# USB3300.net
KiCad netlist of a schematic drawn in Altium Designer
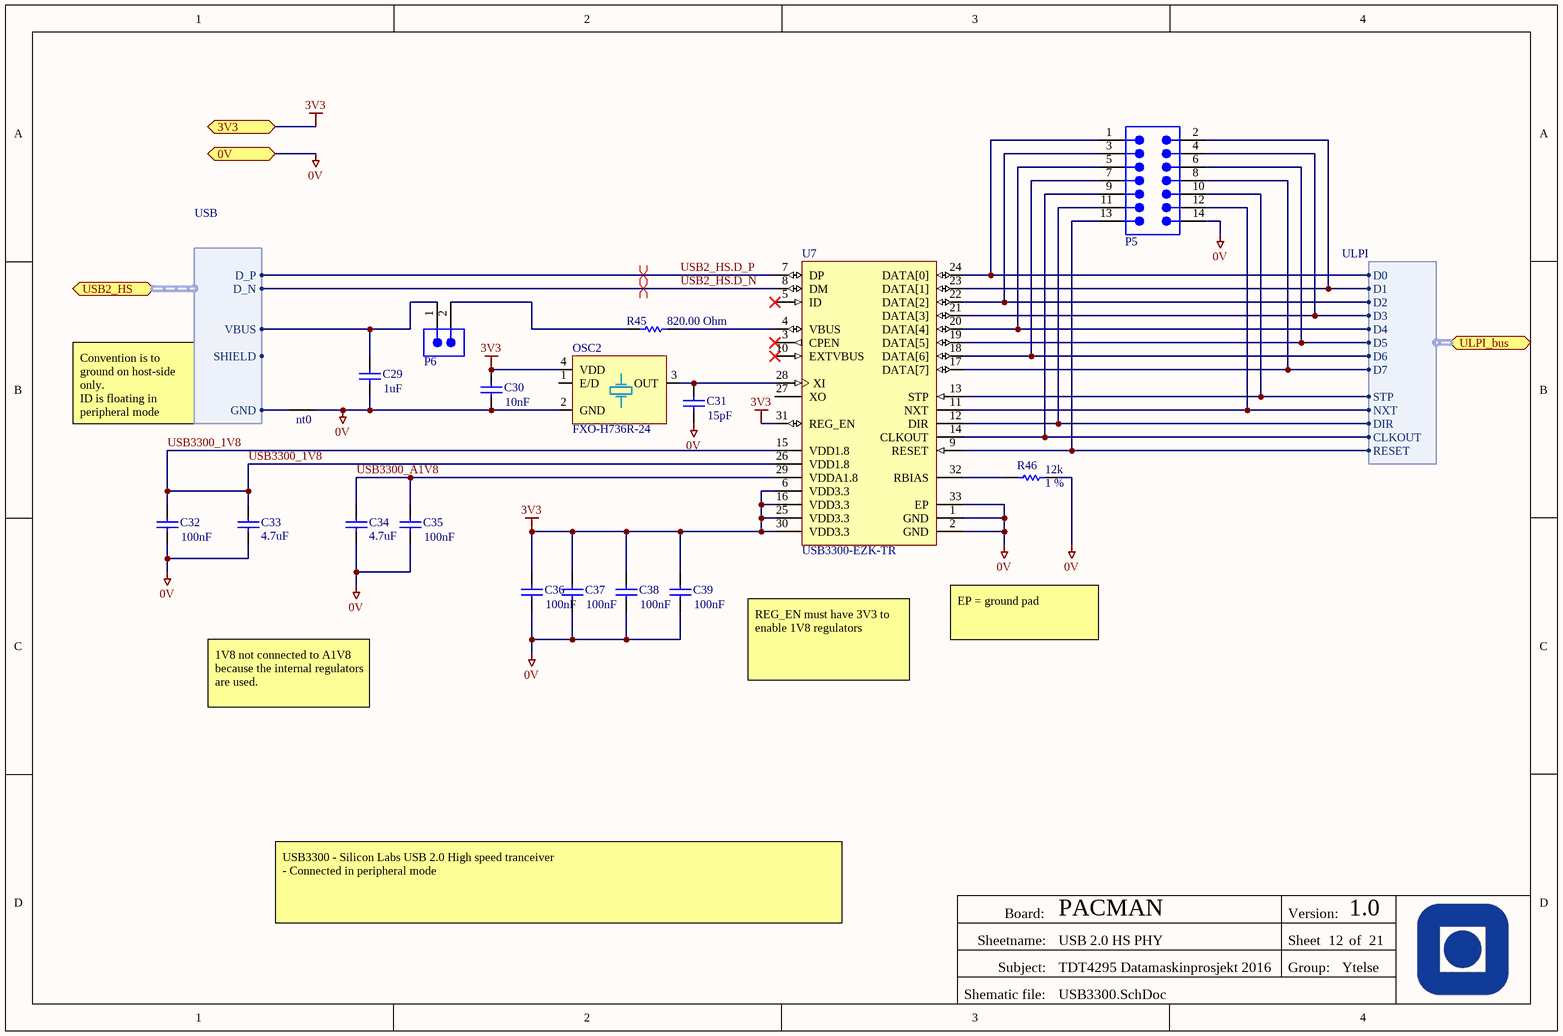
[diagram p0: USB3300.SchDoc]

(export (version "E")
  (design (tool "Eeschema 10.0.6"))
  (components
    (comp (ref "C29")
      (value "1uF")
      (footprint "CAPC0603(1608)100_M")
      (description "CAP 1uF 16V ±5% 0603 (1608 Metric) Thickness 1mm SMD")
      (fields (field (name "TOLERANCE") "Â±5%") (field (name "Comment") "CAP 1uF 16V 0603(1608)"))
      (libsource (lib "Altium Content Vault") (part "CMP-1035-02736-1"))
    )
    (comp (ref "C30")
      (value "10nF")
      (footprint "CAPC0603(1608)100_L")
      (description "CAP 10nF 16V ±1% 0603 (1608 Metric) Thickness 1mm SMD")
      (fields (field (name "TOLERANCE") "Â±1%") (field (name "Comment") "CAP 10nF 16V 0603(1608)"))
      (libsource (lib "Altium Content Vault") (part "CMP-1035-02309-1"))
    )
    (comp (ref "C31")
      (value "15pF")
      (footprint "CAPC0603(1608)100_M")
      (description "CAP 15pF 16V ±0.25pF 0603 (1608 Metric) Thickness 1mm SMD")
      (fields (field (name "TOLERANCE") "Â±0.25pF") (field (name "Comment") "CAP 15pF 16V 0603(1608)"))
      (libsource (lib "Altium Content Vault") (part "CMP-1035-00665-1"))
    )
    (comp (ref "C32")
      (value "100nF")
      (footprint "CAPC0603(1608)100_M")
      (description "CAP 100nF 16V ±5% 0603 (1608 Metric) Thickness 1mm SMD")
      (fields (field (name "TOLERANCE") "Â±5%") (field (name "Comment") "CAP 100nF 16V 0603(1608)"))
      (libsource (lib "Altium Content Vault") (part "CMP-1035-02583-1"))
    )
    (comp (ref "C33")
      (value "4.7uF")
      (footprint "CAPC0603(1608)100_M")
      (description "CAP 4.7uF 16V ±10% 0603 (1608 Metric) Thickness 1mm SMD")
      (fields (field (name "TOLERANCE") "Â±10%") (field (name "Comment") "CAP 4.7uF 16V 0603(1608)"))
      (libsource (lib "Altium Content Vault") (part "CMP-1035-02788-1"))
    )
    (comp (ref "C34")
      (value "4.7uF")
      (footprint "CAPC0603(1608)100_M")
      (description "CAP 4.7uF 16V ±10% 0603 (1608 Metric) Thickness 1mm SMD")
      (fields (field (name "TOLERANCE") "Â±10%") (field (name "Comment") "CAP 4.7uF 16V 0603(1608)"))
      (libsource (lib "Altium Content Vault") (part "CMP-1035-02788-1"))
    )
    (comp (ref "C35")
      (value "100nF")
      (footprint "CAPC0603(1608)100_M")
      (description "CAP 100nF 16V ±5% 0603 (1608 Metric) Thickness 1mm SMD")
      (fields (field (name "TOLERANCE") "Â±5%") (field (name "Comment") "CAP 100nF 16V 0603(1608)"))
      (libsource (lib "Altium Content Vault") (part "CMP-1035-02583-1"))
    )
    (comp (ref "C36")
      (value "100nF")
      (footprint "CAPC0603(1608)100_M")
      (description "CAP 100nF 16V ±5% 0603 (1608 Metric) Thickness 1mm SMD")
      (fields (field (name "TOLERANCE") "Â±5%") (field (name "Comment") "CAP 100nF 16V 0603(1608)"))
      (libsource (lib "Altium Content Vault") (part "CMP-1035-02583-1"))
    )
    (comp (ref "C37")
      (value "100nF")
      (footprint "CAPC0603(1608)100_M")
      (description "CAP 100nF 16V ±5% 0603 (1608 Metric) Thickness 1mm SMD")
      (fields (field (name "TOLERANCE") "Â±5%") (field (name "Comment") "CAP 100nF 16V 0603(1608)"))
      (libsource (lib "Altium Content Vault") (part "CMP-1035-02583-1"))
    )
    (comp (ref "C38")
      (value "100nF")
      (footprint "CAPC0603(1608)100_M")
      (description "CAP 100nF 16V ±5% 0603 (1608 Metric) Thickness 1mm SMD")
      (fields (field (name "TOLERANCE") "Â±5%") (field (name "Comment") "CAP 100nF 16V 0603(1608)"))
      (libsource (lib "Altium Content Vault") (part "CMP-1035-02583-1"))
    )
    (comp (ref "C39")
      (value "100nF")
      (footprint "CAPC0603(1608)100_M")
      (description "CAP 100nF 16V ±5% 0603 (1608 Metric) Thickness 1mm SMD")
      (fields (field (name "TOLERANCE") "Â±5%") (field (name "Comment") "CAP 100nF 16V 0603(1608)"))
      (libsource (lib "Altium Content Vault") (part "CMP-1035-02583-1"))
    )
    (comp (ref "nt0")
      (value "net tie")
      (footprint "net tie")
      (description "used to connect nets without transferring net name")
      (libsource (lib "dmpro16lib") (part "net tie"))
    )
    (comp (ref "OSC2")
      (value "FXO-H736R-24")
      (footprint "FXO-HC73")
      (libsource (lib "dmpro16lib") (part "FXO-H736R-24"))
    )
    (comp (ref "P5")
      (value "HTSW-107-42-F-D")
      (footprint "SMTC-HTSW-107-42-X-D")
      (fields (field (name "MANUFACTURER") "Samtec"))
      (libsource (lib "Altium Content Vault") (part "CMP-1024-00062-1"))
    )
    (comp (ref "P6")
      (value "TSW-102-26-L-S")
      (footprint "SMTC-TSW-102-26-XX-S")
      (description "0.025\" SQ Post Header, Through-hole, Vertical, -55 to 125 degC, 2.54 mm Pitch, 2-Pin, Male, RoHS")
      (fields (field (name "MANUFACTURER") "Samtec"))
      (libsource (lib "Altium Content Vault") (part "CMP-1024-00330-1"))
    )
    (comp (ref "R45")
      (value "820.00 Ohm")
      (footprint "RESC0603(1608)_N")
      (description "820R 0.1W 5% 0603 (1608 Metric)  SMD")
      (fields (field (name "TOLERANCE") "5 %") (field (name "POWER") "0.1 W"))
      (libsource (lib "Altium Content Vault") (part "CMP-1012-00072-1"))
    )
    (comp (ref "R46")
      (value "12k")
      (footprint "RESC0603(1608)_L")
      (description "12K 0.1W 1% 0603 (1608 Metric)  SMD")
      (fields
        (field (name "TOLERANCE") "1 %")
        (field (name "POWER") "0.1 W")
        (field (name "Comment") "12K 1% 0603(1608)")
      )
      (libsource (lib "Altium Content Vault") (part "CMP-1012-00631-1"))
    )
    (comp (ref "U7")
      (value "USB3300-EZK-TR")
      (footprint "MCHP-QFN-32-5x5_V2")
      (fields (field (name "GENERIC PART NUMBER") "USB3300"))
      (libsource (lib "Altium Content Vault") (part "MCHP-USB3300-QFN-32"))
    )
  )
  (nets
    (net (code "3") (name "/CLKOUT") (class "Default")
      (node (ref "P5") (pin "9") (pinfunction "9_9") (pintype "passive"))
      (node (ref "U7") (pin "14") (pinfunction "CLKOUT_14") (pintype "tri_state"))
    )
    (net (code "4") (name "/D0") (class "Default")
      (node (ref "P5") (pin "1") (pinfunction "1_1") (pintype "passive"))
      (node (ref "U7") (pin "24") (pinfunction "DATA[0]_24") (pintype "bidirectional"))
    )
    (net (code "5") (name "/D1") (class "Default")
      (node (ref "P5") (pin "2") (pinfunction "2_2") (pintype "passive"))
      (node (ref "U7") (pin "23") (pinfunction "DATA[1]_23") (pintype "bidirectional"))
    )
    (net (code "6") (name "/D2") (class "Default")
      (node (ref "P5") (pin "3") (pinfunction "3_3") (pintype "passive"))
      (node (ref "U7") (pin "22") (pinfunction "DATA[2]_22") (pintype "bidirectional"))
    )
    (net (code "7") (name "/D3") (class "Default")
      (node (ref "P5") (pin "4") (pinfunction "4_4") (pintype "passive"))
      (node (ref "U7") (pin "21") (pinfunction "DATA[3]_21") (pintype "bidirectional"))
    )
    (net (code "8") (name "/D4") (class "Default")
      (node (ref "P5") (pin "5") (pinfunction "5_5") (pintype "passive"))
      (node (ref "U7") (pin "20") (pinfunction "DATA[4]_20") (pintype "bidirectional"))
    )
    (net (code "9") (name "/D5") (class "Default")
      (node (ref "P5") (pin "6") (pinfunction "6_6") (pintype "passive"))
      (node (ref "U7") (pin "19") (pinfunction "DATA[5]_19") (pintype "bidirectional"))
    )
    (net (code "10") (name "/D6") (class "Default")
      (node (ref "P5") (pin "7") (pinfunction "7_7") (pintype "passive"))
      (node (ref "U7") (pin "18") (pinfunction "DATA[6]_18") (pintype "bidirectional"))
    )
    (net (code "11") (name "/D7") (class "Default")
      (node (ref "P5") (pin "8") (pinfunction "8_8") (pintype "passive"))
      (node (ref "U7") (pin "17") (pinfunction "DATA[7]_17") (pintype "bidirectional"))
    )
    (net (code "12") (name "/DIR") (class "Default")
      (node (ref "P5") (pin "11") (pinfunction "11_11") (pintype "passive"))
      (node (ref "U7") (pin "12") (pinfunction "DIR_12") (pintype "tri_state"))
    )
    (net (code "13") (name "/GND") (class "Default")
      (node (ref "nt0") (pin "0") (pinfunction "0_0") (pintype "passive"))
    )
    (net (code "14") (name "/NXT") (class "Default")
      (node (ref "P5") (pin "12") (pinfunction "12_12") (pintype "passive"))
      (node (ref "U7") (pin "11") (pinfunction "NXT_11") (pintype "tri_state"))
    )
    (net (code "15") (name "/RESET") (class "Default")
      (node (ref "P5") (pin "13") (pinfunction "13_13") (pintype "passive"))
      (node (ref "U7") (pin "9") (pinfunction "RESET_9") (pintype "input"))
    )
    (net (code "16") (name "/STP") (class "Default")
      (node (ref "P5") (pin "10") (pinfunction "10_10") (pintype "passive"))
      (node (ref "U7") (pin "13") (pinfunction "STP_13") (pintype "input"))
    )
    (net (code "17") (name "/USB2_HS.D_N") (class "Default")
      (node (ref "U7") (pin "8") (pinfunction "DM_8") (pintype "bidirectional"))
    )
    (net (code "18") (name "/USB2_HS.D_P") (class "Default")
      (node (ref "U7") (pin "7") (pinfunction "DP_7") (pintype "bidirectional"))
    )
    (net (code "19") (name "/USB3300_1V8") (class "Default")
      (node (ref "C32") (pin "2") (pinfunction "2_2") (pintype "passive"))
      (node (ref "C33") (pin "2") (pinfunction "2_2") (pintype "passive"))
      (node (ref "U7") (pin "15") (pinfunction "VDD1.8_15") (pintype "power_in"))
      (node (ref "U7") (pin "26") (pinfunction "VDD1.8_26") (pintype "power_in"))
    )
    (net (code "20") (name "/USB3300_A1V8") (class "Default")
      (node (ref "C34") (pin "2") (pinfunction "2_2") (pintype "passive"))
      (node (ref "C35") (pin "2") (pinfunction "2_2") (pintype "passive"))
      (node (ref "U7") (pin "29") (pinfunction "VDDA1.8_29") (pintype "power_in"))
    )
    (net (code "21") (name "/VBUS") (class "Default")
      (node (ref "C29") (pin "2") (pinfunction "2_2") (pintype "passive"))
      (node (ref "P6") (pin "1") (pinfunction "1_1") (pintype "passive"))
    )
    (net (code "24") (name "0V") (class "Default")
      (node (ref "C29") (pin "1") (pinfunction "1_1") (pintype "passive"))
      (node (ref "C30") (pin "1") (pinfunction "1_1") (pintype "passive"))
      (node (ref "C31") (pin "1") (pinfunction "1_1") (pintype "passive"))
      (node (ref "C32") (pin "1") (pinfunction "1_1") (pintype "passive"))
      (node (ref "C33") (pin "1") (pinfunction "1_1") (pintype "passive"))
      (node (ref "C34") (pin "1") (pinfunction "1_1") (pintype "passive"))
      (node (ref "C35") (pin "1") (pinfunction "1_1") (pintype "passive"))
      (node (ref "C36") (pin "1") (pinfunction "1_1") (pintype "passive"))
      (node (ref "C37") (pin "1") (pinfunction "1_1") (pintype "passive"))
      (node (ref "C38") (pin "1") (pinfunction "1_1") (pintype "passive"))
      (node (ref "C39") (pin "1") (pinfunction "1_1") (pintype "passive"))
      (node (ref "OSC2") (pin "2") (pinfunction "GND_2") (pintype "passive"))
      (node (ref "P5") (pin "14") (pinfunction "14_14") (pintype "passive"))
      (node (ref "R46") (pin "2") (pinfunction "2_2") (pintype "passive"))
      (node (ref "U7") (pin "1") (pinfunction "GND_1") (pintype "power_in"))
      (node (ref "U7") (pin "2") (pinfunction "GND_2") (pintype "power_in"))
      (node (ref "U7") (pin "33") (pinfunction "EP_33") (pintype "power_in"))
      (node (ref "nt0") (pin "1") (pinfunction "1_1") (pintype "passive"))
    )
    (net (code "25") (name "3V3") (class "Default")
      (node (ref "C30") (pin "2") (pinfunction "2_2") (pintype "passive"))
      (node (ref "C36") (pin "2") (pinfunction "2_2") (pintype "passive"))
      (node (ref "C37") (pin "2") (pinfunction "2_2") (pintype "passive"))
      (node (ref "C38") (pin "2") (pinfunction "2_2") (pintype "passive"))
      (node (ref "C39") (pin "2") (pinfunction "2_2") (pintype "passive"))
      (node (ref "OSC2") (pin "4") (pinfunction "VDD_4") (pintype "passive"))
      (node (ref "U7") (pin "16") (pinfunction "VDD3.3_16") (pintype "power_in"))
      (node (ref "U7") (pin "25") (pinfunction "VDD3.3_25") (pintype "power_in"))
      (node (ref "U7") (pin "30") (pinfunction "VDD3.3_30") (pintype "power_in"))
      (node (ref "U7") (pin "31") (pinfunction "REG_EN_31") (pintype "bidirectional"))
      (node (ref "U7") (pin "6") (pinfunction "VDD3.3_6") (pintype "power_in"))
    )
    (net (code "26") (name "Net-(OSC2-OUT)") (class "Default")
      (node (ref "C31") (pin "2") (pinfunction "2_2") (pintype "passive"))
      (node (ref "OSC2") (pin "3") (pinfunction "OUT_3") (pintype "passive"))
      (node (ref "U7") (pin "28") (pinfunction "XI_28") (pintype "input"))
    )
    (net (code "27") (name "Net-(P6-Pad2)") (class "Default")
      (node (ref "P6") (pin "2") (pinfunction "2_2") (pintype "passive"))
      (node (ref "R45") (pin "1") (pinfunction "1_1") (pintype "passive"))
    )
    (net (code "28") (name "Net-(U7-RBIAS)") (class "Default")
      (node (ref "R46") (pin "1") (pinfunction "1_1") (pintype "passive"))
      (node (ref "U7") (pin "32") (pinfunction "RBIAS_32") (pintype "passive"))
    )
    (net (code "29") (name "Net-(U7-VBUS)") (class "Default")
      (node (ref "R45") (pin "2") (pinfunction "2_2") (pintype "passive"))
      (node (ref "U7") (pin "4") (pinfunction "VBUS_4") (pintype "bidirectional"))
    )
    (net (code "30") (name "unconnected-(OSC2-E{slash}D-Pad1)") (class "Default")
      (node (ref "OSC2") (pin "1") (pinfunction "E/D_1") (pintype "passive"))
    )
    (net (code "31") (name "unconnected-(U7-CPEN-Pad3)") (class "Default")
      (node (ref "U7") (pin "3") (pinfunction "CPEN_3") (pintype "output+no_connect"))
    )
    (net (code "32") (name "unconnected-(U7-EXTVBUS-Pad10)") (class "Default")
      (node (ref "U7") (pin "10") (pinfunction "EXTVBUS_10") (pintype "input+no_connect"))
    )
    (net (code "33") (name "unconnected-(U7-ID-Pad5)") (class "Default")
      (node (ref "U7") (pin "5") (pinfunction "ID_5") (pintype "input+no_connect"))
    )
    (net (code "34") (name "unconnected-(U7-XO-Pad27)") (class "Default")
      (node (ref "U7") (pin "27") (pinfunction "XO_27") (pintype "passive"))
    )
  )
)
